# litebrite2_2.net
KiCad netlist of a schematic drawn in EAGLE
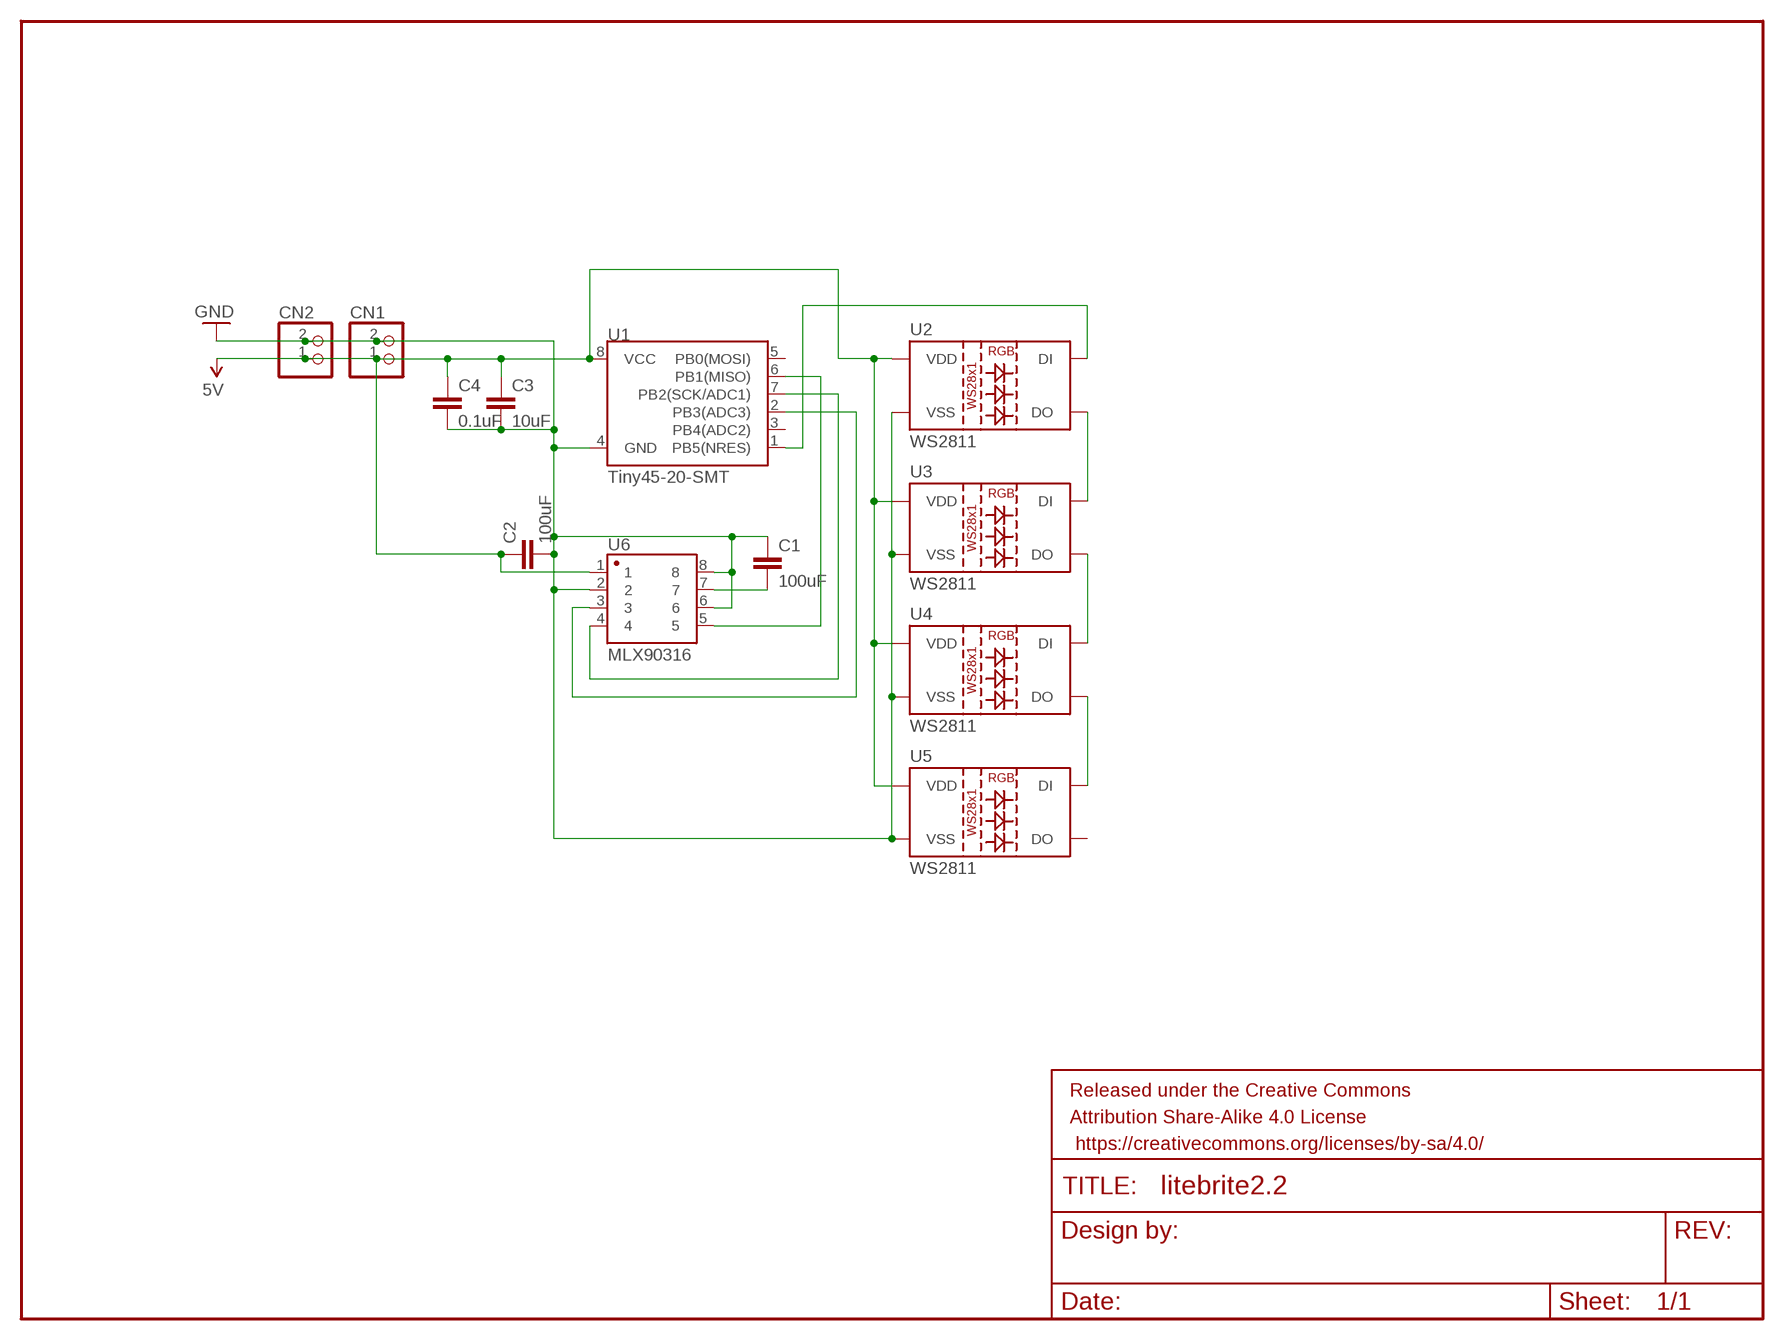
[diagram p0: schematic, sheet 1]

(export (version "E")
  (design (tool "Eeschema 10.0.6"))
  (components
    (comp (ref "C1")
      (value "100uF")
      (footprint "eagle-import:1210")
      (libsource (lib "eagle-import") (part "100UF6.3V20%(1210)"))
    )
    (comp (ref "C2")
      (value "100uF")
      (footprint "eagle-import:1210")
      (libsource (lib "eagle-import") (part "100UF6.3V20%(1210)"))
    )
    (comp (ref "C3")
      (value "10uF")
      (footprint "eagle-import:1206")
      (libsource (lib "eagle-import") (part "10UF-6.3V-20%(1206)"))
    )
    (comp (ref "C4")
      (value "0.1uF")
      (footprint "eagle-import:0402-CAP")
      (libsource (lib "eagle-import") (part "0.1UF-16V(+-10%)(0402)"))
    )
    (comp (ref "CN1")
      (value "JST_2PIN-SMT-RA")
      (footprint "eagle-import:JST-PH-2-SMT-RA")
      (libsource (lib "eagle-import") (part "JST_2PIN-SMT-RA"))
    )
    (comp (ref "CN2")
      (value "JST_2PIN-SMT-RA")
      (footprint "eagle-import:JST-PH-2-SMT-RA")
      (libsource (lib "eagle-import") (part "JST_2PIN-SMT-RA"))
    )
    (comp (ref "FRAME1")
      (value "FRAME-LETTERNO_PACKAGE")
      (footprint "eagle-import:DUMMY")
      (fields (field (name "DESIGNER") "Nobody"))
      (libsource (lib "eagle-import") (part "FRAME-LETTERNO_PACKAGE"))
    )
    (comp (ref "U1")
      (value "Tiny45-20-SMT")
      (footprint "eagle-import:SO08-EIAJ")
      (libsource (lib "eagle-import") (part "ATTINY45TINY45-20-SMT"))
    )
    (comp (ref "U2")
      (value "WS2811")
      (footprint "eagle-import:LED-TRICOLOR-5050-IC")
      (libsource (lib "eagle-import") (part "LED-TRICOLOR-5050-ICWS2811"))
    )
    (comp (ref "U3")
      (value "WS2811")
      (footprint "eagle-import:LED-TRICOLOR-5050-IC")
      (libsource (lib "eagle-import") (part "LED-TRICOLOR-5050-ICWS2811"))
    )
    (comp (ref "U4")
      (value "WS2811")
      (footprint "eagle-import:LED-TRICOLOR-5050-IC")
      (libsource (lib "eagle-import") (part "LED-TRICOLOR-5050-ICWS2811"))
    )
    (comp (ref "U5")
      (value "WS2811")
      (footprint "eagle-import:LED-TRICOLOR-5050-IC")
      (libsource (lib "eagle-import") (part "LED-TRICOLOR-5050-ICWS2811"))
    )
    (comp (ref "U6")
      (value "MLX90316")
      (footprint "eagle-import:SO08")
      (libsource (lib "eagle-import") (part "GENERIC-SOIC8MSGEQ7N-FILTER"))
    )
  )
  (nets
    (net (code "1") (name "5V") (class "Default")
      (node (ref "C2") (pin "1") (pinfunction "1_1") (pintype "passive"))
      (node (ref "C3") (pin "1") (pinfunction "1_1") (pintype "passive"))
      (node (ref "C4") (pin "1") (pinfunction "1_1") (pintype "passive"))
      (node (ref "CN1") (pin "1") (pinfunction "2_1") (pintype "passive"))
      (node (ref "CN2") (pin "1") (pinfunction "2_1") (pintype "passive"))
      (node (ref "U1") (pin "8") (pinfunction "VCC_8") (pintype "bidirectional"))
      (node (ref "U2") (pin "3") (pinfunction "VDD_3") (pintype "bidirectional"))
      (node (ref "U2") (pin "5") (pinfunction "VDD_5") (pintype "bidirectional"))
      (node (ref "U3") (pin "3") (pinfunction "VDD_3") (pintype "bidirectional"))
      (node (ref "U3") (pin "5") (pinfunction "VDD_5") (pintype "bidirectional"))
      (node (ref "U4") (pin "3") (pinfunction "VDD_3") (pintype "bidirectional"))
      (node (ref "U4") (pin "5") (pinfunction "VDD_5") (pintype "bidirectional"))
      (node (ref "U5") (pin "3") (pinfunction "VDD_3") (pintype "bidirectional"))
      (node (ref "U5") (pin "5") (pinfunction "VDD_5") (pintype "bidirectional"))
      (node (ref "U6") (pin "1") (pinfunction "1_1") (pintype "bidirectional"))
    )
    (net (code "2") (name "GND") (class "Default")
      (node (ref "C1") (pin "1") (pinfunction "1_1") (pintype "passive"))
      (node (ref "C2") (pin "2") (pinfunction "2_2") (pintype "passive"))
      (node (ref "C3") (pin "2") (pinfunction "2_2") (pintype "passive"))
      (node (ref "C4") (pin "2") (pinfunction "2_2") (pintype "passive"))
      (node (ref "CN1") (pin "2") (pinfunction "1_2") (pintype "passive"))
      (node (ref "CN2") (pin "2") (pinfunction "1_2") (pintype "passive"))
      (node (ref "U1") (pin "4") (pinfunction "GND_4") (pintype "bidirectional"))
      (node (ref "U2") (pin "6") (pinfunction "VSS_6") (pintype "bidirectional"))
      (node (ref "U3") (pin "6") (pinfunction "VSS_6") (pintype "bidirectional"))
      (node (ref "U4") (pin "6") (pinfunction "VSS_6") (pintype "bidirectional"))
      (node (ref "U5") (pin "6") (pinfunction "VSS_6") (pintype "bidirectional"))
      (node (ref "U6") (pin "2") (pinfunction "2_2") (pintype "bidirectional"))
      (node (ref "U6") (pin "6") (pinfunction "6_6") (pintype "bidirectional"))
      (node (ref "U6") (pin "8") (pinfunction "8_8") (pintype "bidirectional"))
    )
    (net (code "3") (name "Net-(C1-Pad2)") (class "Default")
      (node (ref "C1") (pin "2") (pinfunction "2_2") (pintype "passive"))
      (node (ref "U6") (pin "7") (pinfunction "7_7") (pintype "bidirectional"))
    )
    (net (code "4") (name "Net-(U1-PB1(MISO))") (class "Default")
      (node (ref "U1") (pin "6") (pinfunction "PB1(MISO)_6") (pintype "bidirectional"))
      (node (ref "U6") (pin "5") (pinfunction "5_5") (pintype "bidirectional"))
    )
    (net (code "5") (name "Net-(U1-PB2(SCK{slash}ADC1))") (class "Default")
      (node (ref "U1") (pin "7") (pinfunction "PB2(SCK/ADC1)_7") (pintype "bidirectional"))
      (node (ref "U6") (pin "4") (pinfunction "4_4") (pintype "bidirectional"))
    )
    (net (code "6") (name "Net-(U1-PB3(ADC3))") (class "Default")
      (node (ref "U1") (pin "2") (pinfunction "PB3(ADC3)_2") (pintype "bidirectional"))
      (node (ref "U6") (pin "3") (pinfunction "3_3") (pintype "bidirectional"))
    )
    (net (code "7") (name "Net-(U1-PB5(NRES))") (class "Default")
      (node (ref "U1") (pin "1") (pinfunction "PB5(NRES)_1") (pintype "bidirectional"))
      (node (ref "U2") (pin "2") (pinfunction "DI_2") (pintype "bidirectional"))
    )
    (net (code "8") (name "Net-(U2-DO)") (class "Default")
      (node (ref "U2") (pin "1") (pinfunction "DO_1") (pintype "bidirectional"))
      (node (ref "U3") (pin "2") (pinfunction "DI_2") (pintype "bidirectional"))
    )
    (net (code "9") (name "Net-(U3-DO)") (class "Default")
      (node (ref "U3") (pin "1") (pinfunction "DO_1") (pintype "bidirectional"))
      (node (ref "U4") (pin "2") (pinfunction "DI_2") (pintype "bidirectional"))
    )
    (net (code "10") (name "Net-(U4-DO)") (class "Default")
      (node (ref "U4") (pin "1") (pinfunction "DO_1") (pintype "bidirectional"))
      (node (ref "U5") (pin "2") (pinfunction "DI_2") (pintype "bidirectional"))
    )
    (net (code "11") (name "unconnected-(U1-PB0(MOSI)-Pad5)") (class "Default")
      (node (ref "U1") (pin "5") (pinfunction "PB0(MOSI)_5") (pintype "bidirectional"))
    )
    (net (code "12") (name "unconnected-(U1-PB4(ADC2)-Pad3)") (class "Default")
      (node (ref "U1") (pin "3") (pinfunction "PB4(ADC2)_3") (pintype "bidirectional"))
    )
    (net (code "13") (name "unconnected-(U5-DO-Pad1)") (class "Default")
      (node (ref "U5") (pin "1") (pinfunction "DO_1") (pintype "bidirectional"))
    )
  )
)
